# Condor2_Plugs_REV_C.net
KiCad netlist of a schematic drawn in Altium Designer
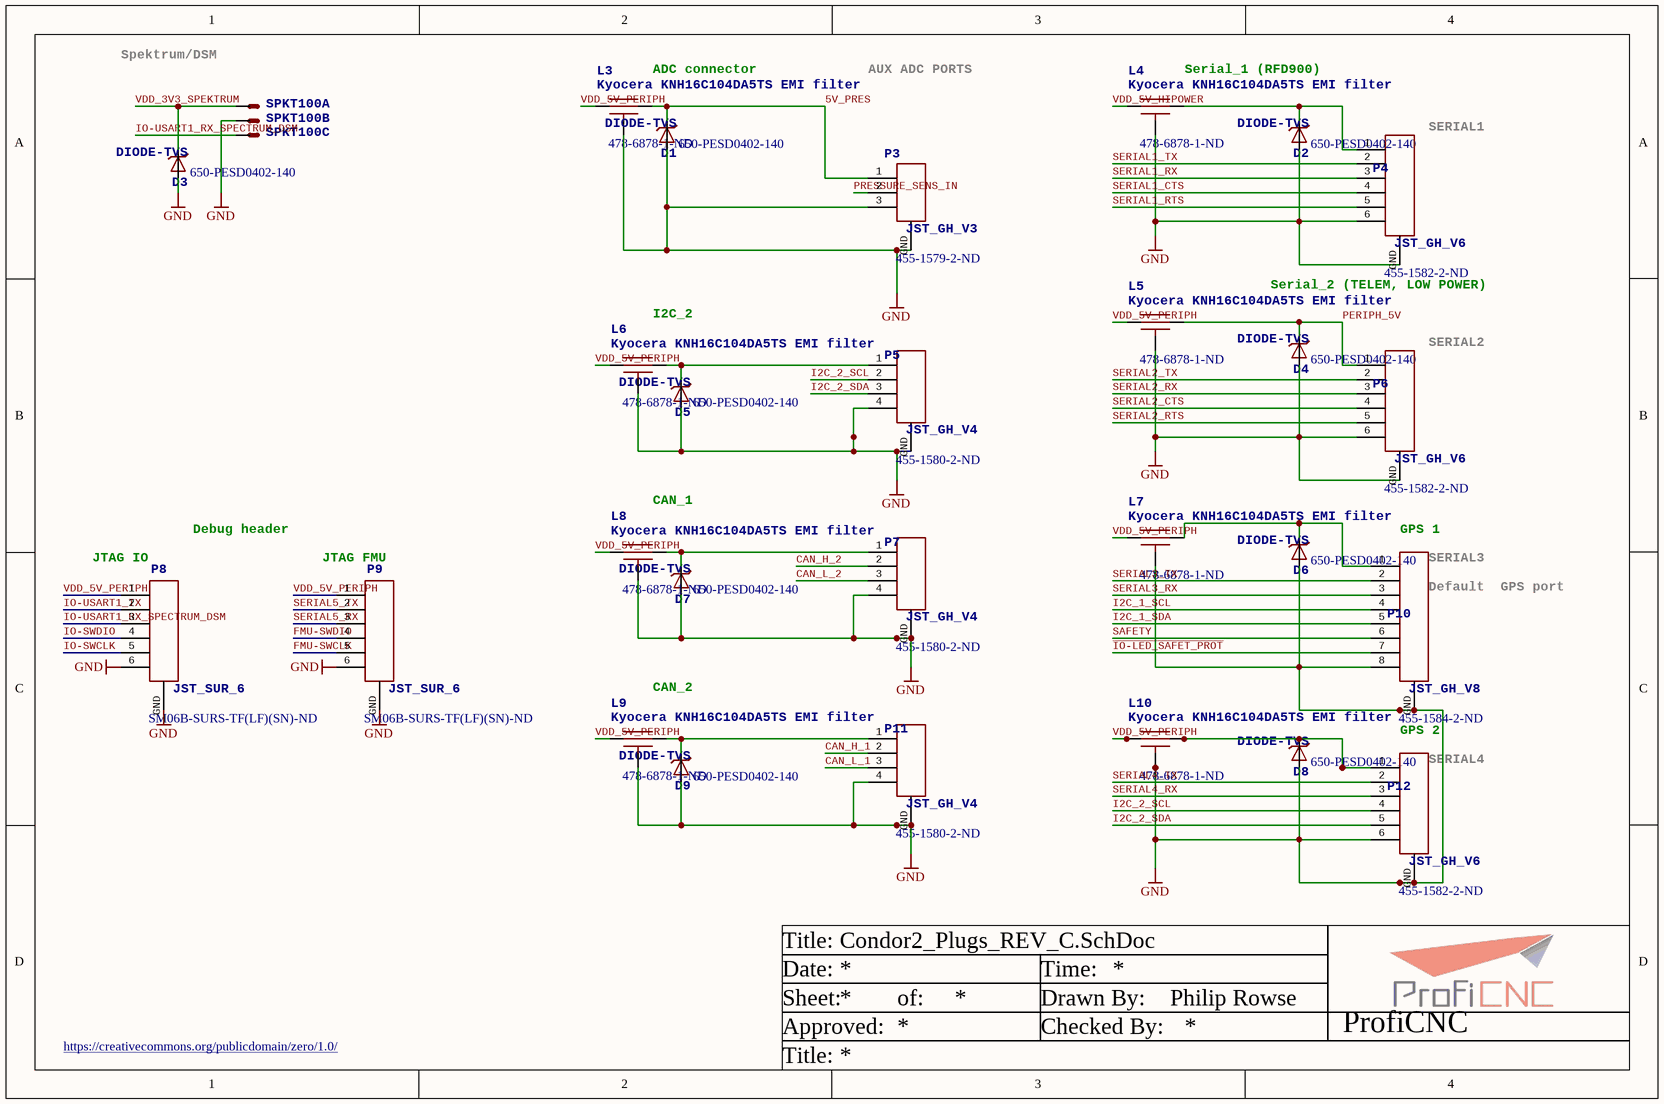
[diagram p0: Condor2_Plugs_REV_C.SchDoc]

(export (version "E")
  (design (tool "Eeschema 10.0.6"))
  (components
    (comp (ref "D1")
      (value "DIODE-TVS")
      (footprint "0402-TVS")
      (description "Diode, TVS, 14VWM, 40VC, 0402, SMD")
      (fields (field (name "SUPPLIER PART NUMBER 1") "650-PESD0402-140"))
      (libsource (lib "CB_REV_C") (part "DIODE-TVS"))
    )
    (comp (ref "D2")
      (value "DIODE-TVS")
      (footprint "0402-TVS")
      (description "Diode, TVS, 14VWM, 40VC, 0402, SMD")
      (fields (field (name "SUPPLIER PART NUMBER 1") "650-PESD0402-140"))
      (libsource (lib "CB_REV_C") (part "DIODE-TVS"))
    )
    (comp (ref "D3")
      (value "DIODE-TVS")
      (footprint "0402-TVS")
      (description "Diode, TVS, 14VWM, 40VC, 0402, SMD")
      (fields (field (name "SUPPLIER PART NUMBER 1") "650-PESD0402-140"))
      (libsource (lib "CB_REV_C") (part "DIODE-TVS"))
    )
    (comp (ref "D4")
      (value "DIODE-TVS")
      (footprint "0402-TVS")
      (description "Diode, TVS, 14VWM, 40VC, 0402, SMD")
      (fields (field (name "SUPPLIER PART NUMBER 1") "650-PESD0402-140"))
      (libsource (lib "CB_REV_C") (part "DIODE-TVS"))
    )
    (comp (ref "D5")
      (value "DIODE-TVS")
      (footprint "0402-TVS")
      (description "Diode, TVS, 14VWM, 40VC, 0402, SMD")
      (fields (field (name "SUPPLIER PART NUMBER 1") "650-PESD0402-140"))
      (libsource (lib "CB_REV_C") (part "DIODE-TVS"))
    )
    (comp (ref "D6")
      (value "DIODE-TVS")
      (footprint "0402-TVS")
      (description "Diode, TVS, 14VWM, 40VC, 0402, SMD")
      (fields (field (name "SUPPLIER PART NUMBER 1") "650-PESD0402-140"))
      (libsource (lib "CB_REV_C") (part "DIODE-TVS"))
    )
    (comp (ref "D7")
      (value "DIODE-TVS")
      (footprint "0402-TVS")
      (description "Diode, TVS, 14VWM, 40VC, 0402, SMD")
      (fields (field (name "SUPPLIER PART NUMBER 1") "650-PESD0402-140"))
      (libsource (lib "CB_REV_C") (part "DIODE-TVS"))
    )
    (comp (ref "D8")
      (value "DIODE-TVS")
      (footprint "0402-TVS")
      (description "Diode, TVS, 14VWM, 40VC, 0402, SMD")
      (fields (field (name "SUPPLIER PART NUMBER 1") "650-PESD0402-140"))
      (libsource (lib "CB_REV_C") (part "DIODE-TVS"))
    )
    (comp (ref "D9")
      (value "DIODE-TVS")
      (footprint "0402-TVS")
      (description "Diode, TVS, 14VWM, 40VC, 0402, SMD")
      (fields (field (name "SUPPLIER PART NUMBER 1") "650-PESD0402-140"))
      (libsource (lib "CB_REV_C") (part "DIODE-TVS"))
    )
    (comp (ref "L3")
      (value "Kyocera KNH16C104DA5TS EMI filter")
      (footprint "KYOCERA-KNH16-DA")
      (description "Capacitor, Filter, 0.1uF, 25V, 2A, 0603, SMD")
      (fields (field (name "SUPPLIER PART NUMBER 1") "478-6878-1-ND"))
      (libsource (lib "CB_REV_C") (part "KNH16C104DA5TS"))
    )
    (comp (ref "L4")
      (value "Kyocera KNH16C104DA5TS EMI filter")
      (footprint "KYOCERA-KNH16-DA")
      (description "Capacitor, Filter, 0.1uF, 25V, 2A, 0603, SMD")
      (fields (field (name "SUPPLIER PART NUMBER 1") "478-6878-1-ND"))
      (libsource (lib "CB_REV_C") (part "KNH16C104DA5TS"))
    )
    (comp (ref "L5")
      (value "Kyocera KNH16C104DA5TS EMI filter")
      (footprint "KYOCERA-KNH16-DA")
      (description "Capacitor, Filter, 0.1uF, 25V, 2A, 0603, SMD")
      (fields (field (name "SUPPLIER PART NUMBER 1") "478-6878-1-ND"))
      (libsource (lib "CB_REV_C") (part "KNH16C104DA5TS"))
    )
    (comp (ref "L6")
      (value "Kyocera KNH16C104DA5TS EMI filter")
      (footprint "KYOCERA-KNH16-DA")
      (description "Capacitor, Filter, 0.1uF, 25V, 2A, 0603, SMD")
      (fields (field (name "SUPPLIER PART NUMBER 1") "478-6878-1-ND"))
      (libsource (lib "CB_REV_C") (part "KNH16C104DA5TS"))
    )
    (comp (ref "L7")
      (value "Kyocera KNH16C104DA5TS EMI filter")
      (footprint "KYOCERA-KNH16-DA")
      (description "Capacitor, Filter, 0.1uF, 25V, 2A, 0603, SMD")
      (fields (field (name "SUPPLIER PART NUMBER 1") "478-6878-1-ND"))
      (libsource (lib "CB_REV_C") (part "KNH16C104DA5TS"))
    )
    (comp (ref "L8")
      (value "Kyocera KNH16C104DA5TS EMI filter")
      (footprint "KYOCERA-KNH16-DA")
      (description "Capacitor, Filter, 0.1uF, 25V, 2A, 0603, SMD")
      (fields (field (name "SUPPLIER PART NUMBER 1") "478-6878-1-ND"))
      (libsource (lib "CB_REV_C") (part "KNH16C104DA5TS"))
    )
    (comp (ref "L9")
      (value "Kyocera KNH16C104DA5TS EMI filter")
      (footprint "KYOCERA-KNH16-DA")
      (description "Capacitor, Filter, 0.1uF, 25V, 2A, 0603, SMD")
      (fields (field (name "SUPPLIER PART NUMBER 1") "478-6878-1-ND"))
      (libsource (lib "CB_REV_C") (part "KNH16C104DA5TS"))
    )
    (comp (ref "L10")
      (value "Kyocera KNH16C104DA5TS EMI filter")
      (footprint "KYOCERA-KNH16-DA")
      (description "Capacitor, Filter, 0.1uF, 25V, 2A, 0603, SMD")
      (fields (field (name "SUPPLIER PART NUMBER 1") "478-6878-1-ND"))
      (libsource (lib "CB_REV_C") (part "KNH16C104DA5TS"))
    )
    (comp (ref "P3")
      (value "JST_GH_V3")
      (footprint "JST_GH_V3")
      (description "BM03B-GHS-TBT")
      (fields (field (name "SUPPLIER PART NUMBER 1") "455-1579-2-ND"))
      (libsource (lib "CB_REV_C") (part "JST_GH_V3"))
    )
    (comp (ref "P4")
      (value "JST_GH_V6")
      (footprint "JST_GH_V6")
      (description "BM06B-GHS-TBT")
      (fields (field (name "SUPPLIER PART NUMBER 1") "455-1582-2-ND"))
      (libsource (lib "CB_REV_C") (part "JST_GH_V6"))
    )
    (comp (ref "P5")
      (value "JST_GH_V4")
      (footprint "JST_GH_V4")
      (description "BM04B-GHS-TBT")
      (fields (field (name "SUPPLIER PART NUMBER 1") "455-1580-2-ND"))
      (libsource (lib "CB_REV_C") (part "JST_GH_V4"))
    )
    (comp (ref "P6")
      (value "JST_GH_V6")
      (footprint "JST_GH_V6")
      (description "BM06B-GHS-TBT")
      (fields (field (name "SUPPLIER PART NUMBER 1") "455-1582-2-ND"))
      (libsource (lib "CB_REV_C") (part "JST_GH_V6"))
    )
    (comp (ref "P7")
      (value "JST_GH_V4")
      (footprint "JST_GH_V4")
      (description "BM04B-GHS-TBT")
      (fields (field (name "SUPPLIER PART NUMBER 1") "455-1580-2-ND"))
      (libsource (lib "CB_REV_C") (part "JST_GH_V4"))
    )
    (comp (ref "P8")
      (value "JST_SUR_6")
      (footprint "JST_SUR_H6")
      (description "Connector, Header, 6Pos, .8mm IDC, R/A, SMD, Tin")
      (fields (field (name "SUPPLIER PART NUMBER 1") "SM06B-SURS-TF(LF)(SN)-ND"))
      (libsource (lib "CB_REV_C") (part "JST_SUR_6"))
    )
    (comp (ref "P9")
      (value "JST_SUR_6")
      (footprint "JST_SUR_H6")
      (description "Connector, Header, 6Pos, .8mm IDC, R/A, SMD, Tin")
      (fields (field (name "SUPPLIER PART NUMBER 1") "SM06B-SURS-TF(LF)(SN)-ND"))
      (libsource (lib "CB_REV_C") (part "JST_SUR_6"))
    )
    (comp (ref "P10")
      (value "JST_GH_V8")
      (footprint "JST_GH_V8")
      (description "BM08B-GHS-TBT")
      (fields (field (name "SUPPLIER PART NUMBER 1") "455-1584-2-ND"))
      (libsource (lib "CB_REV_C") (part "JST_GH_V8"))
    )
    (comp (ref "P11")
      (value "JST_GH_V4")
      (footprint "JST_GH_V4")
      (description "BM04B-GHS-TBT")
      (fields (field (name "SUPPLIER PART NUMBER 1") "455-1580-2-ND"))
      (libsource (lib "CB_REV_C") (part "JST_GH_V4"))
    )
    (comp (ref "P12")
      (value "JST_GH_V6")
      (footprint "JST_GH_V6")
      (description "BM06B-GHS-TBT")
      (fields (field (name "SUPPLIER PART NUMBER 1") "455-1582-2-ND"))
      (libsource (lib "CB_REV_C") (part "JST_GH_V6"))
    )
    (comp (ref "SPKT100")
      (value "CONN_SPEKTRUM_RX-TH")
      (footprint "B3B-ZR")
      (description "Spektrum RX connector; JST ZH series S3B-ZR-SM4A-TF")
      (fields (field (name "PARTNO") "B3B-ZR(LF)(SN)"))
      (libsource (lib "CB_REV_C") (part "CONN_SPEKTRUM_RX-TH"))
    )
  )
  (nets
    (net (code "1") (name "/5V_PRES") (class "Default")
      (node (ref "D1") (pin "C") (pinfunction "C_C") (pintype "passive"))
      (node (ref "L3") (pin "P$2") (pinfunction "P$2_P$2") (pintype "passive"))
      (node (ref "P3") (pin "1") (pinfunction "1_1") (pintype "passive"))
    )
    (net (code "2") (name "/CAN_H_1") (class "Default")
      (node (ref "P11") (pin "2") (pinfunction "2_2") (pintype "passive"))
    )
    (net (code "3") (name "/CAN_H_2") (class "Default")
      (node (ref "P7") (pin "2") (pinfunction "2_2") (pintype "passive"))
    )
    (net (code "4") (name "/CAN_L_1") (class "Default")
      (node (ref "P11") (pin "3") (pinfunction "3_3") (pintype "passive"))
    )
    (net (code "5") (name "/CAN_L_2") (class "Default")
      (node (ref "P7") (pin "3") (pinfunction "3_3") (pintype "passive"))
    )
    (net (code "6") (name "/FMU-SWCLK") (class "Default")
      (node (ref "P9") (pin "5") (pinfunction "5_5") (pintype "passive"))
    )
    (net (code "7") (name "/FMU-SWDIO") (class "Default")
      (node (ref "P9") (pin "4") (pinfunction "4_4") (pintype "passive"))
    )
    (net (code "8") (name "/I2C_1_SCL") (class "Default")
      (node (ref "P10") (pin "4") (pinfunction "4_4") (pintype "passive"))
    )
    (net (code "9") (name "/I2C_1_SDA") (class "Default")
      (node (ref "P10") (pin "5") (pinfunction "5_5") (pintype "passive"))
    )
    (net (code "10") (name "/I2C_2_SCL") (class "Default")
      (node (ref "P12") (pin "4") (pinfunction "4_4") (pintype "passive"))
      (node (ref "P5") (pin "2") (pinfunction "2_2") (pintype "passive"))
    )
    (net (code "11") (name "/I2C_2_SDA") (class "Default")
      (node (ref "P12") (pin "5") (pinfunction "5_5") (pintype "passive"))
      (node (ref "P5") (pin "3") (pinfunction "3_3") (pintype "passive"))
    )
    (net (code "12") (name "/IO-SWCLK") (class "Default")
      (node (ref "P8") (pin "5") (pinfunction "5_5") (pintype "passive"))
    )
    (net (code "13") (name "/IO-SWDIO") (class "Default")
      (node (ref "P8") (pin "4") (pinfunction "4_4") (pintype "passive"))
    )
    (net (code "14") (name "/IO-USART1_RX_SPECTRUM_DSM") (class "Default")
      (node (ref "P8") (pin "3") (pinfunction "3_3") (pintype "passive"))
      (node (ref "SPKT100") (pin "1") (pinfunction "S_1") (pintype "passive"))
    )
    (net (code "15") (name "/IO-USART1_TX") (class "Default")
      (node (ref "P8") (pin "2") (pinfunction "2_2") (pintype "passive"))
    )
    (net (code "16") (name "/PERIPH_5V") (class "Default")
      (node (ref "D4") (pin "C") (pinfunction "C_C") (pintype "passive"))
      (node (ref "L5") (pin "P$2") (pinfunction "P$2_P$2") (pintype "passive"))
      (node (ref "P6") (pin "1") (pinfunction "1_1") (pintype "passive"))
    )
    (net (code "17") (name "/PRESSURE_SENS_IN") (class "Default")
      (node (ref "P3") (pin "2") (pinfunction "2_2") (pintype "passive"))
    )
    (net (code "18") (name "/SAFETY") (class "Default")
      (node (ref "P10") (pin "6") (pinfunction "6_6") (pintype "passive"))
    )
    (net (code "19") (name "/SERIAL1_CTS") (class "Default")
      (node (ref "P4") (pin "4") (pinfunction "4_4") (pintype "passive"))
    )
    (net (code "20") (name "/SERIAL1_RTS") (class "Default")
      (node (ref "P4") (pin "5") (pinfunction "5_5") (pintype "passive"))
    )
    (net (code "21") (name "/SERIAL1_RX") (class "Default")
      (node (ref "P4") (pin "3") (pinfunction "3_3") (pintype "passive"))
    )
    (net (code "22") (name "/SERIAL1_TX") (class "Default")
      (node (ref "P4") (pin "2") (pinfunction "2_2") (pintype "passive"))
    )
    (net (code "23") (name "/SERIAL2_CTS") (class "Default")
      (node (ref "P6") (pin "4") (pinfunction "4_4") (pintype "passive"))
    )
    (net (code "24") (name "/SERIAL2_RTS") (class "Default")
      (node (ref "P6") (pin "5") (pinfunction "5_5") (pintype "passive"))
    )
    (net (code "25") (name "/SERIAL2_RX") (class "Default")
      (node (ref "P6") (pin "3") (pinfunction "3_3") (pintype "passive"))
    )
    (net (code "26") (name "/SERIAL2_TX") (class "Default")
      (node (ref "P6") (pin "2") (pinfunction "2_2") (pintype "passive"))
    )
    (net (code "27") (name "/SERIAL3_RX") (class "Default")
      (node (ref "P10") (pin "3") (pinfunction "3_3") (pintype "passive"))
    )
    (net (code "28") (name "/SERIAL3_TX") (class "Default")
      (node (ref "P10") (pin "2") (pinfunction "2_2") (pintype "passive"))
    )
    (net (code "29") (name "/SERIAL4_RX") (class "Default")
      (node (ref "P12") (pin "3") (pinfunction "3_3") (pintype "passive"))
    )
    (net (code "30") (name "/SERIAL4_TX") (class "Default")
      (node (ref "P12") (pin "2") (pinfunction "2_2") (pintype "passive"))
    )
    (net (code "31") (name "/SERIAL5_RX") (class "Default")
      (node (ref "P9") (pin "3") (pinfunction "3_3") (pintype "passive"))
    )
    (net (code "32") (name "/SERIAL5_TX") (class "Default")
      (node (ref "P9") (pin "2") (pinfunction "2_2") (pintype "passive"))
    )
    (net (code "33") (name "/VDD_3V3_SPEKTRUM") (class "Default")
      (node (ref "D3") (pin "C") (pinfunction "C_C") (pintype "passive"))
      (node (ref "SPKT100") (pin "3") (pinfunction "S_3") (pintype "passive"))
    )
    (net (code "34") (name "/VDD_5V_HIPOWER") (class "Default")
      (node (ref "L4") (pin "P$1") (pinfunction "P$1_P$1") (pintype "passive"))
    )
    (net (code "35") (name "/VDD_5V_PERIPH") (class "Default")
      (node (ref "L10") (pin "P$1") (pinfunction "P$1_P$1") (pintype "passive"))
      (node (ref "L3") (pin "P$1") (pinfunction "P$1_P$1") (pintype "passive"))
      (node (ref "L5") (pin "P$1") (pinfunction "P$1_P$1") (pintype "passive"))
      (node (ref "L6") (pin "P$1") (pinfunction "P$1_P$1") (pintype "passive"))
      (node (ref "L7") (pin "P$1") (pinfunction "P$1_P$1") (pintype "passive"))
      (node (ref "L8") (pin "P$1") (pinfunction "P$1_P$1") (pintype "passive"))
      (node (ref "L9") (pin "P$1") (pinfunction "P$1_P$1") (pintype "passive"))
      (node (ref "P8") (pin "1") (pinfunction "1_1") (pintype "passive"))
      (node (ref "P9") (pin "1") (pinfunction "1_1") (pintype "passive"))
    )
    (net (code "36") (name "/~{IO-LED_SAFET_PROT}") (class "Default")
      (node (ref "P10") (pin "7") (pinfunction "7_7") (pintype "passive"))
    )
    (net (code "37") (name "GND") (class "Default")
      (node (ref "D1") (pin "A") (pinfunction "A_A") (pintype "passive"))
      (node (ref "D2") (pin "A") (pinfunction "A_A") (pintype "passive"))
      (node (ref "D3") (pin "A") (pinfunction "A_A") (pintype "passive"))
      (node (ref "D4") (pin "A") (pinfunction "A_A") (pintype "passive"))
      (node (ref "D5") (pin "A") (pinfunction "A_A") (pintype "passive"))
      (node (ref "D6") (pin "A") (pinfunction "A_A") (pintype "passive"))
      (node (ref "D7") (pin "A") (pinfunction "A_A") (pintype "passive"))
      (node (ref "D8") (pin "A") (pinfunction "A_A") (pintype "passive"))
      (node (ref "D9") (pin "A") (pinfunction "A_A") (pintype "passive"))
      (node (ref "L10") (pin "GND") (pinfunction "GND_GND") (pintype "passive"))
      (node (ref "L3") (pin "GND") (pinfunction "GND_GND") (pintype "passive"))
      (node (ref "L4") (pin "GND") (pinfunction "GND_GND") (pintype "passive"))
      (node (ref "L5") (pin "GND") (pinfunction "GND_GND") (pintype "passive"))
      (node (ref "L6") (pin "GND") (pinfunction "GND_GND") (pintype "passive"))
      (node (ref "L7") (pin "GND") (pinfunction "GND_GND") (pintype "passive"))
      (node (ref "L8") (pin "GND") (pinfunction "GND_GND") (pintype "passive"))
      (node (ref "L9") (pin "GND") (pinfunction "GND_GND") (pintype "passive"))
      (node (ref "P10") (pin "8") (pinfunction "8_8") (pintype "passive"))
      (node (ref "P10") (pin "GND") (pinfunction "GND_GND") (pintype "passive"))
      (node (ref "P11") (pin "4") (pinfunction "4_4") (pintype "passive"))
      (node (ref "P11") (pin "GND") (pinfunction "GND_GND") (pintype "passive"))
      (node (ref "P12") (pin "6") (pinfunction "6_6") (pintype "passive"))
      (node (ref "P12") (pin "GND") (pinfunction "GND_GND") (pintype "passive"))
      (node (ref "P3") (pin "3") (pinfunction "3_3") (pintype "passive"))
      (node (ref "P3") (pin "GND") (pinfunction "GND_GND") (pintype "passive"))
      (node (ref "P4") (pin "6") (pinfunction "6_6") (pintype "passive"))
      (node (ref "P4") (pin "GND") (pinfunction "GND_GND") (pintype "passive"))
      (node (ref "P5") (pin "4") (pinfunction "4_4") (pintype "passive"))
      (node (ref "P5") (pin "GND") (pinfunction "GND_GND") (pintype "passive"))
      (node (ref "P6") (pin "6") (pinfunction "6_6") (pintype "passive"))
      (node (ref "P6") (pin "GND") (pinfunction "GND_GND") (pintype "passive"))
      (node (ref "P7") (pin "4") (pinfunction "4_4") (pintype "passive"))
      (node (ref "P7") (pin "GND") (pinfunction "GND_GND") (pintype "passive"))
      (node (ref "P8") (pin "6") (pinfunction "6_6") (pintype "passive"))
      (node (ref "P8") (pin "GND") (pinfunction "GND_GND") (pintype "passive"))
      (node (ref "P9") (pin "6") (pinfunction "6_6") (pintype "passive"))
      (node (ref "P9") (pin "GND") (pinfunction "GND_GND") (pintype "passive"))
      (node (ref "SPKT100") (pin "2") (pinfunction "S_2") (pintype "passive"))
    )
    (net (code "38") (name "Net-(D2-PadC)") (class "Default")
      (node (ref "D2") (pin "C") (pinfunction "C_C") (pintype "passive"))
      (node (ref "L4") (pin "P$2") (pinfunction "P$2_P$2") (pintype "passive"))
      (node (ref "P4") (pin "1") (pinfunction "1_1") (pintype "passive"))
    )
    (net (code "39") (name "Net-(D5-PadC)") (class "Default")
      (node (ref "D5") (pin "C") (pinfunction "C_C") (pintype "passive"))
      (node (ref "L6") (pin "P$2") (pinfunction "P$2_P$2") (pintype "passive"))
      (node (ref "P5") (pin "1") (pinfunction "1_1") (pintype "passive"))
    )
    (net (code "40") (name "Net-(D6-PadC)") (class "Default")
      (node (ref "D6") (pin "C") (pinfunction "C_C") (pintype "passive"))
      (node (ref "L7") (pin "P$2") (pinfunction "P$2_P$2") (pintype "passive"))
      (node (ref "P10") (pin "1") (pinfunction "1_1") (pintype "passive"))
    )
    (net (code "41") (name "Net-(D7-PadC)") (class "Default")
      (node (ref "D7") (pin "C") (pinfunction "C_C") (pintype "passive"))
      (node (ref "L8") (pin "P$2") (pinfunction "P$2_P$2") (pintype "passive"))
      (node (ref "P7") (pin "1") (pinfunction "1_1") (pintype "passive"))
    )
    (net (code "42") (name "Net-(D8-PadC)") (class "Default")
      (node (ref "D8") (pin "C") (pinfunction "C_C") (pintype "passive"))
      (node (ref "L10") (pin "P$2") (pinfunction "P$2_P$2") (pintype "passive"))
      (node (ref "P12") (pin "1") (pinfunction "1_1") (pintype "passive"))
    )
    (net (code "43") (name "Net-(D9-PadC)") (class "Default")
      (node (ref "D9") (pin "C") (pinfunction "C_C") (pintype "passive"))
      (node (ref "L9") (pin "P$2") (pinfunction "P$2_P$2") (pintype "passive"))
      (node (ref "P11") (pin "1") (pinfunction "1_1") (pintype "passive"))
    )
  )
)
